# 04-Sensors.net
KiCad netlist of a schematic drawn in Altium Designer
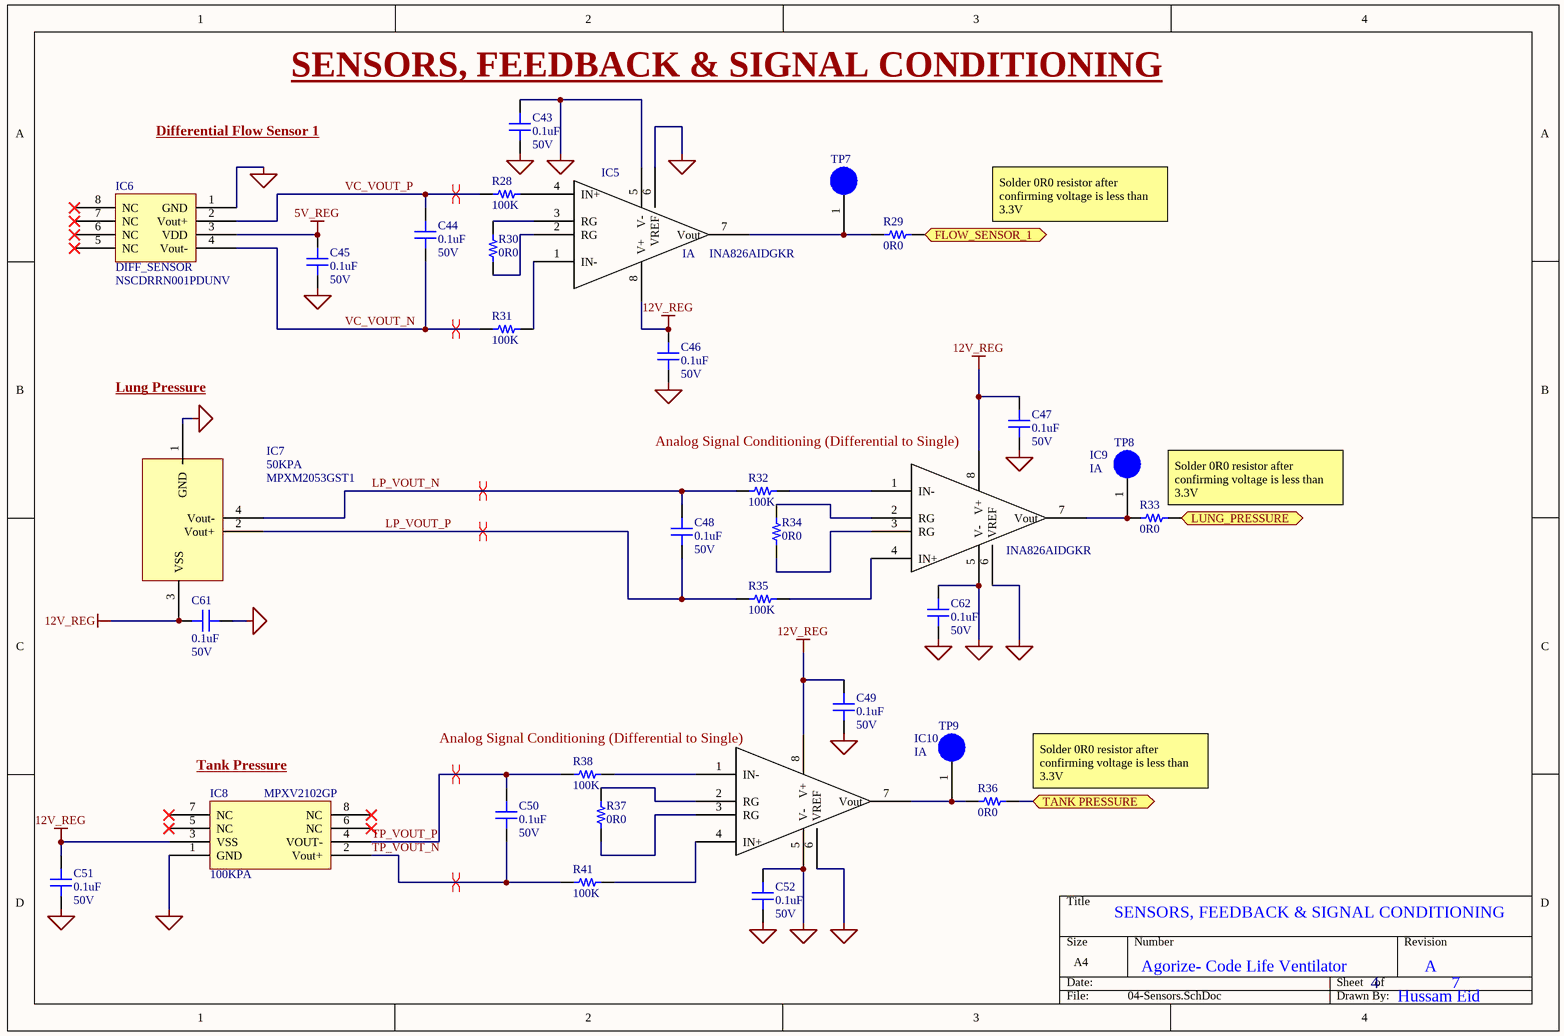
[diagram p0: 04-Sensors.SchDoc]

(export (version "E")
  (design (tool "Eeschema 10.0.6"))
  (components
    (comp (ref "C43")
      (value "0.1uF")
      (footprint "CAP 0603/1608")
      (description "CAP CER 0.1UF 50V X7R 0603")
      (fields (field (name "TOLERANCE") "20%") (field (name "VOLTAGE RATING") "50V"))
      (libsource (lib "Celestial Library Database") (part "Capacitor"))
    )
    (comp (ref "C44")
      (value "0.1uF")
      (footprint "CAP 0603/1608")
      (description "CAP CER 0.1UF 50V X7R 0603")
      (fields (field (name "TOLERANCE") "20%") (field (name "VOLTAGE RATING") "50V"))
      (libsource (lib "Celestial Library Database") (part "Capacitor"))
    )
    (comp (ref "C45")
      (value "0.1uF")
      (footprint "CAP 0603/1608")
      (description "CAP CER 0.1UF 50V X7R 0603")
      (fields (field (name "TOLERANCE") "20%") (field (name "VOLTAGE RATING") "50V"))
      (libsource (lib "Celestial Library Database") (part "Capacitor"))
    )
    (comp (ref "C46")
      (value "0.1uF")
      (footprint "CAP 0603/1608")
      (description "CAP CER 0.1UF 50V X7R 0603")
      (fields (field (name "TOLERANCE") "20%") (field (name "VOLTAGE RATING") "50V"))
      (libsource (lib "Celestial Library Database") (part "Capacitor"))
    )
    (comp (ref "C47")
      (value "0.1uF")
      (footprint "CAP 0603/1608")
      (description "CAP CER 0.1UF 50V X7R 0603")
      (fields (field (name "TOLERANCE") "20%") (field (name "VOLTAGE RATING") "50V"))
      (libsource (lib "Celestial Library Database") (part "Capacitor"))
    )
    (comp (ref "C48")
      (value "0.1uF")
      (footprint "CAP 0603/1608")
      (description "CAP CER 0.1UF 50V X7R 0603")
      (fields (field (name "TOLERANCE") "20%") (field (name "VOLTAGE RATING") "50V"))
      (libsource (lib "Celestial Library Database") (part "Capacitor"))
    )
    (comp (ref "C49")
      (value "0.1uF")
      (footprint "CAP 0603/1608")
      (description "CAP CER 0.1UF 50V X7R 0603")
      (fields (field (name "TOLERANCE") "20%") (field (name "VOLTAGE RATING") "50V"))
      (libsource (lib "Celestial Library Database") (part "Capacitor"))
    )
    (comp (ref "C50")
      (value "0.1uF")
      (footprint "CAP 0603/1608")
      (description "CAP CER 0.1UF 50V X7R 0603")
      (fields (field (name "TOLERANCE") "20%") (field (name "VOLTAGE RATING") "50V"))
      (libsource (lib "Celestial Library Database") (part "Capacitor"))
    )
    (comp (ref "C51")
      (value "0.1uF")
      (footprint "CAP 0603/1608")
      (description "CAP CER 0.1UF 50V X7R 0603")
      (fields (field (name "TOLERANCE") "20%") (field (name "VOLTAGE RATING") "50V"))
      (libsource (lib "Celestial Library Database") (part "Capacitor"))
    )
    (comp (ref "C52")
      (value "0.1uF")
      (footprint "CAP 0603/1608")
      (description "CAP CER 0.1UF 50V X7R 0603")
      (fields (field (name "TOLERANCE") "20%") (field (name "VOLTAGE RATING") "50V"))
      (libsource (lib "Celestial Library Database") (part "Capacitor"))
    )
    (comp (ref "C61")
      (value "0.1uF")
      (footprint "CAP 0603/1608")
      (description "CAP CER 0.1UF 50V X7R 0603")
      (fields (field (name "TOLERANCE") "20%") (field (name "VOLTAGE RATING") "50V"))
      (libsource (lib "Celestial Library Database") (part "Capacitor"))
    )
    (comp (ref "C62")
      (value "0.1uF")
      (footprint "CAP 0603/1608")
      (description "CAP CER 0.1UF 50V X7R 0603")
      (fields (field (name "TOLERANCE") "20%") (field (name "VOLTAGE RATING") "50V"))
      (libsource (lib "Celestial Library Database") (part "Capacitor"))
    )
    (comp (ref "IC5")
      (value "IA")
      (footprint "SOP65P490X110-8N")
      (description "IC INST AMP 1 CIRCUIT 8VSSOP")
      (fields (field (name "MANUFACTURER PART NUMBER 1") "INA826AIDGKR"))
      (libsource (lib "Schlib1") (part "IA"))
    )
    (comp (ref "IC6")
      (value "DIFF_SENSOR")
      (footprint "DIP8_Pressure_Sense")
      (description "SENSOR PRESS DIFF 1PSI")
      (fields (field (name "MANUFACTURER PART NUMBER 1") "NSCDRRN001PDUNV"))
      (libsource (lib "Schlib1") (part "DIFF_SENSOR"))
    )
    (comp (ref "IC7")
      (value "50KPA")
      (footprint "DPAK127P1219X1008-5N")
      (description "SENS PRESSURE 7.25 PSI MAX MPAK")
      (fields (field (name "MANUFACTURER PART NUMBER 1") "MPXM2053GST1"))
      (libsource (lib "Schlib1") (part "Pressure Sensor"))
    )
    (comp (ref "IC8")
      (value "100KPA")
      (footprint "SOP127P600-8N")
      (description "SENSOR GAUGE PRESS 14.5PSI MAX")
      (fields (field (name "MANUFACTURER PART NUMBER 1") "MPXV2102GP"))
      (libsource (lib "Schlib1") (part "100KPA Pressure Sensor"))
    )
    (comp (ref "IC9")
      (value "IA")
      (footprint "SOP65P490X110-8N")
      (description "IC INST AMP 1 CIRCUIT 8VSSOP")
      (fields (field (name "MANUFACTURER PART NUMBER 1") "INA826AIDGKR"))
      (libsource (lib "Schlib1") (part "IA"))
    )
    (comp (ref "IC10")
      (value "IA")
      (footprint "SOP65P490X110-8N")
      (description "IC INST AMP 1 CIRCUIT 8VSSOP")
      (libsource (lib "Schlib1") (part "IA"))
    )
    (comp (ref "R28")
      (value "100K")
      (footprint "RES 0603/1608")
      (description "RES SMD100K OHM 0.5% 1/16W 0603")
      (fields (field (name "TOLERANCE") "0.5%"))
      (libsource (lib "Celestial Library Database") (part "Resistor"))
    )
    (comp (ref "R29")
      (value "0R0")
      (footprint "RES 0603/1608")
      (description "RES SMD 0 OHM JUMPER 1/10W 0603")
      (fields (field (name "TOLERANCE") "0%"))
      (libsource (lib "Celestial Library Database") (part "Resistor"))
    )
    (comp (ref "R30")
      (value "0R0")
      (footprint "RES 0603/1608")
      (description "RES SMD 0 OHM JUMPER 1/10W 0603")
      (fields (field (name "TOLERANCE") "0%"))
      (libsource (lib "Celestial Library Database") (part "Resistor"))
    )
    (comp (ref "R31")
      (value "100K")
      (footprint "RES 0603/1608")
      (description "RES SMD100K OHM 0.5% 1/16W 0603")
      (fields (field (name "TOLERANCE") "0.5%"))
      (libsource (lib "Celestial Library Database") (part "Resistor"))
    )
    (comp (ref "R32")
      (value "100K")
      (footprint "RES 0603/1608")
      (description "RES SMD100K OHM 0.5% 1/16W 0603")
      (fields (field (name "TOLERANCE") "0.5%"))
      (libsource (lib "Celestial Library Database") (part "Resistor"))
    )
    (comp (ref "R33")
      (value "0R0")
      (footprint "RES 0603/1608")
      (description "RES SMD 0 OHM JUMPER 1/10W 0603")
      (fields (field (name "TOLERANCE") "0%"))
      (libsource (lib "Celestial Library Database") (part "Resistor"))
    )
    (comp (ref "R34")
      (value "0R0")
      (footprint "RES 0603/1608")
      (description "RES SMD 0 OHM JUMPER 1/10W 0603")
      (fields (field (name "TOLERANCE") "0%"))
      (libsource (lib "Celestial Library Database") (part "Resistor"))
    )
    (comp (ref "R35")
      (value "100K")
      (footprint "RES 0603/1608")
      (description "RES SMD100K OHM 0.5% 1/16W 0603")
      (fields (field (name "TOLERANCE") "0.5%"))
      (libsource (lib "Celestial Library Database") (part "Resistor"))
    )
    (comp (ref "R36")
      (value "0R0")
      (footprint "RES 0603/1608")
      (description "RES SMD 0 OHM JUMPER 1/10W 0603")
      (fields (field (name "TOLERANCE") "0%"))
      (libsource (lib "Celestial Library Database") (part "Resistor"))
    )
    (comp (ref "R37")
      (value "0R0")
      (footprint "RES 0603/1608")
      (description "RES SMD 0 OHM JUMPER 1/10W 0603")
      (fields (field (name "TOLERANCE") "0%"))
      (libsource (lib "Celestial Library Database") (part "Resistor"))
    )
    (comp (ref "R38")
      (value "100K")
      (footprint "RES 0603/1608")
      (description "RES SMD100K OHM 0.5% 1/16W 0603")
      (fields (field (name "TOLERANCE") "0.5%"))
      (libsource (lib "Celestial Library Database") (part "Resistor"))
    )
    (comp (ref "R41")
      (value "100K")
      (footprint "RES 0603/1608")
      (description "RES SMD100K OHM 0.5% 1/16W 0603")
      (fields (field (name "TOLERANCE") "0.5%"))
      (libsource (lib "Celestial Library Database") (part "Resistor"))
    )
    (comp (ref "TP7")
      (value "TP")
      (footprint "TP")
      (description "Test Point")
      (libsource (lib "Schlib1") (part "TP"))
    )
    (comp (ref "TP8")
      (value "TP")
      (footprint "TP")
      (description "Test Point")
      (libsource (lib "Schlib1") (part "TP"))
    )
    (comp (ref "TP9")
      (value "TP")
      (footprint "TP")
      (description "Test Point")
      (libsource (lib "Schlib1") (part "TP"))
    )
  )
  (nets
    (net (code "1") (name "/FLOW_SENSOR_1") (class "Default")
      (node (ref "R29") (pin "1") (pinfunction "1_1") (pintype "passive"))
    )
    (net (code "2") (name "/LP_VOUT_N") (class "Default")
      (node (ref "C48") (pin "2") (pinfunction "2_2") (pintype "passive"))
      (node (ref "IC7") (pin "4") (pinfunction "Vout-_4") (pintype "passive"))
      (node (ref "R32") (pin "2") (pinfunction "2_2") (pintype "passive"))
    )
    (net (code "3") (name "/LP_VOUT_P") (class "Default")
      (node (ref "C48") (pin "1") (pinfunction "1_1") (pintype "passive"))
      (node (ref "IC7") (pin "2") (pinfunction "Vout+_2") (pintype "passive"))
      (node (ref "R35") (pin "2") (pinfunction "2_2") (pintype "passive"))
    )
    (net (code "4") (name "/LUNG_PRESSURE") (class "Default")
      (node (ref "R33") (pin "1") (pinfunction "1_1") (pintype "passive"))
    )
    (net (code "5") (name "/TANK PRESSURE") (class "Default")
      (node (ref "R36") (pin "1") (pinfunction "1_1") (pintype "passive"))
    )
    (net (code "6") (name "/TP_VOUT_N") (class "Default")
      (node (ref "C50") (pin "1") (pinfunction "1_1") (pintype "passive"))
      (node (ref "IC8") (pin "2") (pinfunction "Vout+_2") (pintype "passive"))
      (node (ref "R41") (pin "2") (pinfunction "2_2") (pintype "passive"))
    )
    (net (code "7") (name "/TP_VOUT_P") (class "Default")
      (node (ref "C50") (pin "2") (pinfunction "2_2") (pintype "passive"))
      (node (ref "IC8") (pin "4") (pinfunction "VOUT-_4") (pintype "passive"))
      (node (ref "R38") (pin "2") (pinfunction "2_2") (pintype "passive"))
    )
    (net (code "8") (name "/VC_VOUT_N") (class "Default")
      (node (ref "C44") (pin "1") (pinfunction "1_1") (pintype "passive"))
      (node (ref "IC6") (pin "4") (pinfunction "Vout-_4") (pintype "passive"))
      (node (ref "R31") (pin "2") (pinfunction "2_2") (pintype "passive"))
    )
    (net (code "9") (name "/VC_VOUT_P") (class "Default")
      (node (ref "C44") (pin "2") (pinfunction "2_2") (pintype "passive"))
      (node (ref "IC6") (pin "2") (pinfunction "Vout+_2") (pintype "passive"))
      (node (ref "R28") (pin "2") (pinfunction "2_2") (pintype "passive"))
    )
    (net (code "10") (name "5V_REG") (class "Default")
      (node (ref "C45") (pin "1") (pinfunction "1_1") (pintype "passive"))
      (node (ref "IC6") (pin "3") (pinfunction "VDD_3") (pintype "passive"))
    )
    (net (code "11") (name "12V_REG") (class "Default")
      (node (ref "C46") (pin "2") (pinfunction "2_2") (pintype "passive"))
      (node (ref "C47") (pin "2") (pinfunction "2_2") (pintype "passive"))
      (node (ref "C49") (pin "2") (pinfunction "2_2") (pintype "passive"))
      (node (ref "C51") (pin "2") (pinfunction "2_2") (pintype "passive"))
      (node (ref "C61") (pin "1") (pinfunction "1_1") (pintype "passive"))
      (node (ref "IC10") (pin "8") (pinfunction "V+_8") (pintype "passive"))
      (node (ref "IC5") (pin "8") (pinfunction "V+_8") (pintype "passive"))
      (node (ref "IC7") (pin "3") (pinfunction "VSS_3") (pintype "passive"))
      (node (ref "IC8") (pin "3") (pinfunction "VSS_3") (pintype "passive"))
      (node (ref "IC9") (pin "8") (pinfunction "V+_8") (pintype "passive"))
    )
    (net (code "12") (name "COM") (class "Default")
      (node (ref "C43") (pin "1") (pinfunction "1_1") (pintype "passive"))
      (node (ref "C43") (pin "2") (pinfunction "2_2") (pintype "passive"))
      (node (ref "C45") (pin "2") (pinfunction "2_2") (pintype "passive"))
      (node (ref "C46") (pin "1") (pinfunction "1_1") (pintype "passive"))
      (node (ref "C47") (pin "1") (pinfunction "1_1") (pintype "passive"))
      (node (ref "C49") (pin "1") (pinfunction "1_1") (pintype "passive"))
      (node (ref "C51") (pin "1") (pinfunction "1_1") (pintype "passive"))
      (node (ref "C52") (pin "1") (pinfunction "1_1") (pintype "passive"))
      (node (ref "C52") (pin "2") (pinfunction "2_2") (pintype "passive"))
      (node (ref "C61") (pin "2") (pinfunction "2_2") (pintype "passive"))
      (node (ref "C62") (pin "1") (pinfunction "1_1") (pintype "passive"))
      (node (ref "C62") (pin "2") (pinfunction "2_2") (pintype "passive"))
      (node (ref "IC10") (pin "5") (pinfunction "V-_5") (pintype "passive"))
      (node (ref "IC10") (pin "6") (pinfunction "VREF_6") (pintype "passive"))
      (node (ref "IC5") (pin "5") (pinfunction "V-_5") (pintype "passive"))
      (node (ref "IC5") (pin "6") (pinfunction "VREF_6") (pintype "passive"))
      (node (ref "IC6") (pin "1") (pinfunction "GND_1") (pintype "passive"))
      (node (ref "IC7") (pin "1") (pinfunction "GND_1") (pintype "passive"))
      (node (ref "IC8") (pin "1") (pinfunction "GND_1") (pintype "passive"))
      (node (ref "IC9") (pin "5") (pinfunction "V-_5") (pintype "passive"))
      (node (ref "IC9") (pin "6") (pinfunction "VREF_6") (pintype "passive"))
    )
    (net (code "13") (name "Net-(IC5-IN+)") (class "Default")
      (node (ref "IC5") (pin "4") (pinfunction "IN+_4") (pintype "passive"))
      (node (ref "R28") (pin "1") (pinfunction "1_1") (pintype "passive"))
    )
    (net (code "14") (name "Net-(IC5-IN-)") (class "Default")
      (node (ref "IC5") (pin "1") (pinfunction "IN-_1") (pintype "passive"))
      (node (ref "R31") (pin "1") (pinfunction "1_1") (pintype "passive"))
    )
    (net (code "15") (name "Net-(IC5-RG-Pad2)") (class "Default")
      (node (ref "IC5") (pin "2") (pinfunction "RG_2") (pintype "passive"))
      (node (ref "R30") (pin "1") (pinfunction "1_1") (pintype "passive"))
    )
    (net (code "16") (name "Net-(IC5-RG-Pad3)") (class "Default")
      (node (ref "IC5") (pin "3") (pinfunction "RG_3") (pintype "passive"))
      (node (ref "R30") (pin "2") (pinfunction "2_2") (pintype "passive"))
    )
    (net (code "17") (name "Net-(IC5-Vout)") (class "Default")
      (node (ref "IC5") (pin "7") (pinfunction "Vout_7") (pintype "passive"))
      (node (ref "R29") (pin "2") (pinfunction "2_2") (pintype "passive"))
      (node (ref "TP7") (pin "1") (pinfunction "1_1") (pintype "passive"))
    )
    (net (code "18") (name "Net-(IC9-IN+)") (class "Default")
      (node (ref "IC9") (pin "4") (pinfunction "IN+_4") (pintype "passive"))
      (node (ref "R35") (pin "1") (pinfunction "1_1") (pintype "passive"))
    )
    (net (code "19") (name "Net-(IC9-IN-)") (class "Default")
      (node (ref "IC9") (pin "1") (pinfunction "IN-_1") (pintype "passive"))
      (node (ref "R32") (pin "1") (pinfunction "1_1") (pintype "passive"))
    )
    (net (code "20") (name "Net-(IC9-RG-Pad2)") (class "Default")
      (node (ref "IC9") (pin "2") (pinfunction "RG_2") (pintype "passive"))
      (node (ref "R34") (pin "2") (pinfunction "2_2") (pintype "passive"))
    )
    (net (code "21") (name "Net-(IC9-RG-Pad3)") (class "Default")
      (node (ref "IC9") (pin "3") (pinfunction "RG_3") (pintype "passive"))
      (node (ref "R34") (pin "1") (pinfunction "1_1") (pintype "passive"))
    )
    (net (code "22") (name "Net-(IC9-Vout)") (class "Default")
      (node (ref "IC9") (pin "7") (pinfunction "Vout_7") (pintype "passive"))
      (node (ref "R33") (pin "2") (pinfunction "2_2") (pintype "passive"))
      (node (ref "TP8") (pin "1") (pinfunction "1_1") (pintype "passive"))
    )
    (net (code "23") (name "Net-(IC10-IN+)") (class "Default")
      (node (ref "IC10") (pin "4") (pinfunction "IN+_4") (pintype "passive"))
      (node (ref "R41") (pin "1") (pinfunction "1_1") (pintype "passive"))
    )
    (net (code "24") (name "Net-(IC10-IN-)") (class "Default")
      (node (ref "IC10") (pin "1") (pinfunction "IN-_1") (pintype "passive"))
      (node (ref "R38") (pin "1") (pinfunction "1_1") (pintype "passive"))
    )
    (net (code "25") (name "Net-(IC10-RG-Pad2)") (class "Default")
      (node (ref "IC10") (pin "2") (pinfunction "RG_2") (pintype "passive"))
      (node (ref "R37") (pin "2") (pinfunction "2_2") (pintype "passive"))
    )
    (net (code "26") (name "Net-(IC10-RG-Pad3)") (class "Default")
      (node (ref "IC10") (pin "3") (pinfunction "RG_3") (pintype "passive"))
      (node (ref "R37") (pin "1") (pinfunction "1_1") (pintype "passive"))
    )
    (net (code "27") (name "Net-(IC10-Vout)") (class "Default")
      (node (ref "IC10") (pin "7") (pinfunction "Vout_7") (pintype "passive"))
      (node (ref "R36") (pin "2") (pinfunction "2_2") (pintype "passive"))
      (node (ref "TP9") (pin "1") (pinfunction "1_1") (pintype "passive"))
    )
    (net (code "28") (name "unconnected-(IC6-NC-Pad5)") (class "Default")
      (node (ref "IC6") (pin "5") (pinfunction "NC_5") (pintype "passive+no_connect"))
    )
    (net (code "29") (name "unconnected-(IC6-NC-Pad6)") (class "Default")
      (node (ref "IC6") (pin "6") (pinfunction "NC_6") (pintype "passive+no_connect"))
    )
    (net (code "30") (name "unconnected-(IC6-NC-Pad7)") (class "Default")
      (node (ref "IC6") (pin "7") (pinfunction "NC_7") (pintype "passive+no_connect"))
    )
    (net (code "31") (name "unconnected-(IC6-NC-Pad8)") (class "Default")
      (node (ref "IC6") (pin "8") (pinfunction "NC_8") (pintype "passive+no_connect"))
    )
    (net (code "32") (name "unconnected-(IC8-NC-Pad5)") (class "Default")
      (node (ref "IC8") (pin "5") (pinfunction "NC_5") (pintype "passive+no_connect"))
    )
    (net (code "33") (name "unconnected-(IC8-NC-Pad6)") (class "Default")
      (node (ref "IC8") (pin "6") (pinfunction "NC_6") (pintype "passive+no_connect"))
    )
    (net (code "34") (name "unconnected-(IC8-NC-Pad7)") (class "Default")
      (node (ref "IC8") (pin "7") (pinfunction "NC_7") (pintype "passive+no_connect"))
    )
    (net (code "35") (name "unconnected-(IC8-NC-Pad8)") (class "Default")
      (node (ref "IC8") (pin "8") (pinfunction "NC_8") (pintype "passive+no_connect"))
    )
  )
)
